# daughter_v1.net
KiCad netlist of a schematic drawn in EAGLE
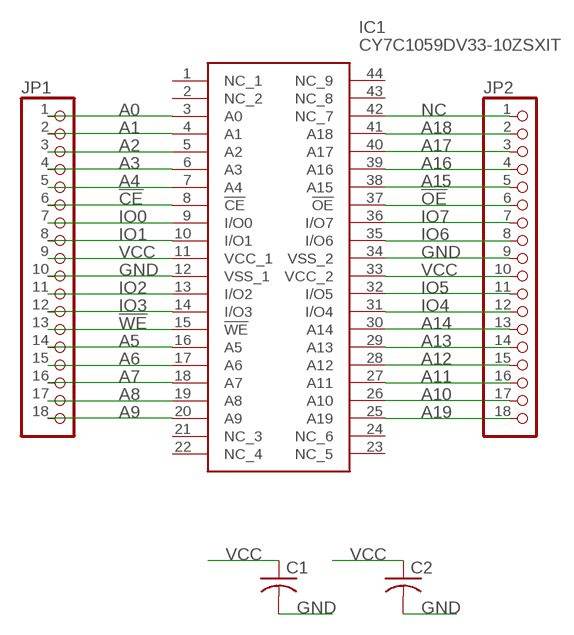
[diagram p0: schematic, sheet 1]

(export (version "E")
  (design (tool "Eeschema 10.0.6"))
  (components
    (comp (ref "C1")
      (value "C-USC0805")
      (footprint "eagle-import:C0805")
      (libsource (lib "eagle-import") (part "C-USC0805"))
    )
    (comp (ref "C2")
      (value "C-USC0805")
      (footprint "eagle-import:C0805")
      (libsource (lib "eagle-import") (part "C-USC0805"))
    )
    (comp (ref "IC1")
      (value "CY7C1059DV33-10ZSXIT")
      (footprint "eagle-import:SOP80P1184X119-44N")
      (fields (field (name "MOUSER_PART_NUMBER") "727-C1059DV3310ZSXIT"))
      (libsource (lib "eagle-import") (part "CY7C1059DV33-10ZSXIT"))
    )
    (comp (ref "JP1")
      (value "PINHD-1X18")
      (footprint "eagle-import:1X18")
      (libsource (lib "eagle-import") (part "PINHD-1X18"))
    )
    (comp (ref "JP2")
      (value "PINHD-1X18")
      (footprint "eagle-import:1X18")
      (libsource (lib "eagle-import") (part "PINHD-1X18"))
    )
  )
  (nets
    (net (code "1") (name "/A0") (class "Default")
      (node (ref "IC1") (pin "3") (pinfunction "A0_3") (pintype "bidirectional"))
      (node (ref "JP1") (pin "1") (pinfunction "1_1") (pintype "passive"))
    )
    (net (code "2") (name "/A1") (class "Default")
      (node (ref "IC1") (pin "4") (pinfunction "A1_4") (pintype "bidirectional"))
      (node (ref "JP1") (pin "2") (pinfunction "2_2") (pintype "passive"))
    )
    (net (code "3") (name "/A2") (class "Default")
      (node (ref "IC1") (pin "5") (pinfunction "A2_5") (pintype "bidirectional"))
      (node (ref "JP1") (pin "3") (pinfunction "3_3") (pintype "passive"))
    )
    (net (code "4") (name "/A3") (class "Default")
      (node (ref "IC1") (pin "6") (pinfunction "A3_6") (pintype "bidirectional"))
      (node (ref "JP1") (pin "4") (pinfunction "4_4") (pintype "passive"))
    )
    (net (code "5") (name "/A4") (class "Default")
      (node (ref "IC1") (pin "7") (pinfunction "A4_7") (pintype "bidirectional"))
      (node (ref "JP1") (pin "5") (pinfunction "5_5") (pintype "passive"))
    )
    (net (code "6") (name "/A5") (class "Default")
      (node (ref "IC1") (pin "16") (pinfunction "A5_16") (pintype "bidirectional"))
      (node (ref "JP1") (pin "14") (pinfunction "14_14") (pintype "passive"))
    )
    (net (code "7") (name "/A6") (class "Default")
      (node (ref "IC1") (pin "17") (pinfunction "A6_17") (pintype "bidirectional"))
      (node (ref "JP1") (pin "15") (pinfunction "15_15") (pintype "passive"))
    )
    (net (code "8") (name "/A7") (class "Default")
      (node (ref "IC1") (pin "18") (pinfunction "A7_18") (pintype "bidirectional"))
      (node (ref "JP1") (pin "16") (pinfunction "16_16") (pintype "passive"))
    )
    (net (code "9") (name "/A8") (class "Default")
      (node (ref "IC1") (pin "19") (pinfunction "A8_19") (pintype "bidirectional"))
      (node (ref "JP1") (pin "17") (pinfunction "17_17") (pintype "passive"))
    )
    (net (code "10") (name "/A9") (class "Default")
      (node (ref "IC1") (pin "20") (pinfunction "A9_20") (pintype "bidirectional"))
      (node (ref "JP1") (pin "18") (pinfunction "18_18") (pintype "passive"))
    )
    (net (code "11") (name "/A10") (class "Default")
      (node (ref "IC1") (pin "26") (pinfunction "A10_26") (pintype "bidirectional"))
      (node (ref "JP2") (pin "17") (pinfunction "17_17") (pintype "passive"))
    )
    (net (code "12") (name "/A11") (class "Default")
      (node (ref "IC1") (pin "27") (pinfunction "A11_27") (pintype "bidirectional"))
      (node (ref "JP2") (pin "16") (pinfunction "16_16") (pintype "passive"))
    )
    (net (code "13") (name "/A12") (class "Default")
      (node (ref "IC1") (pin "28") (pinfunction "A12_28") (pintype "bidirectional"))
      (node (ref "JP2") (pin "15") (pinfunction "15_15") (pintype "passive"))
    )
    (net (code "14") (name "/A13") (class "Default")
      (node (ref "IC1") (pin "29") (pinfunction "A13_29") (pintype "bidirectional"))
      (node (ref "JP2") (pin "14") (pinfunction "14_14") (pintype "passive"))
    )
    (net (code "15") (name "/A14") (class "Default")
      (node (ref "IC1") (pin "30") (pinfunction "A14_30") (pintype "bidirectional"))
      (node (ref "JP2") (pin "13") (pinfunction "13_13") (pintype "passive"))
    )
    (net (code "16") (name "/A15") (class "Default")
      (node (ref "IC1") (pin "38") (pinfunction "A15_38") (pintype "bidirectional"))
      (node (ref "JP2") (pin "5") (pinfunction "5_5") (pintype "passive"))
    )
    (net (code "17") (name "/A16") (class "Default")
      (node (ref "IC1") (pin "39") (pinfunction "A16_39") (pintype "bidirectional"))
      (node (ref "JP2") (pin "4") (pinfunction "4_4") (pintype "passive"))
    )
    (net (code "18") (name "/A17") (class "Default")
      (node (ref "IC1") (pin "40") (pinfunction "A17_40") (pintype "bidirectional"))
      (node (ref "JP2") (pin "3") (pinfunction "3_3") (pintype "passive"))
    )
    (net (code "19") (name "/A18") (class "Default")
      (node (ref "IC1") (pin "41") (pinfunction "A18_41") (pintype "bidirectional"))
      (node (ref "JP2") (pin "2") (pinfunction "2_2") (pintype "passive"))
    )
    (net (code "20") (name "/A19") (class "Default")
      (node (ref "IC1") (pin "25") (pinfunction "A19_25") (pintype "bidirectional"))
      (node (ref "JP2") (pin "18") (pinfunction "18_18") (pintype "passive"))
    )
    (net (code "21") (name "/GND") (class "Default")
      (node (ref "C1") (pin "2") (pinfunction "2_2") (pintype "passive"))
      (node (ref "C2") (pin "2") (pinfunction "2_2") (pintype "passive"))
      (node (ref "IC1") (pin "12") (pinfunction "VSS_1_12") (pintype "bidirectional"))
      (node (ref "IC1") (pin "34") (pinfunction "VSS_2_34") (pintype "bidirectional"))
      (node (ref "JP1") (pin "10") (pinfunction "10_10") (pintype "passive"))
      (node (ref "JP2") (pin "9") (pinfunction "9_9") (pintype "passive"))
    )
    (net (code "22") (name "/IO0") (class "Default")
      (node (ref "IC1") (pin "9") (pinfunction "I/O0_9") (pintype "bidirectional"))
      (node (ref "JP1") (pin "7") (pinfunction "7_7") (pintype "passive"))
    )
    (net (code "23") (name "/IO1") (class "Default")
      (node (ref "IC1") (pin "10") (pinfunction "I/O1_10") (pintype "bidirectional"))
      (node (ref "JP1") (pin "8") (pinfunction "8_8") (pintype "passive"))
    )
    (net (code "24") (name "/IO2") (class "Default")
      (node (ref "IC1") (pin "13") (pinfunction "I/O2_13") (pintype "bidirectional"))
      (node (ref "JP1") (pin "11") (pinfunction "11_11") (pintype "passive"))
    )
    (net (code "25") (name "/IO3") (class "Default")
      (node (ref "IC1") (pin "14") (pinfunction "I/O3_14") (pintype "bidirectional"))
      (node (ref "JP1") (pin "12") (pinfunction "12_12") (pintype "passive"))
    )
    (net (code "26") (name "/IO4") (class "Default")
      (node (ref "IC1") (pin "31") (pinfunction "I/O4_31") (pintype "bidirectional"))
      (node (ref "JP2") (pin "12") (pinfunction "12_12") (pintype "passive"))
    )
    (net (code "27") (name "/IO5") (class "Default")
      (node (ref "IC1") (pin "32") (pinfunction "I/O5_32") (pintype "bidirectional"))
      (node (ref "JP2") (pin "11") (pinfunction "11_11") (pintype "passive"))
    )
    (net (code "28") (name "/IO6") (class "Default")
      (node (ref "IC1") (pin "35") (pinfunction "I/O6_35") (pintype "bidirectional"))
      (node (ref "JP2") (pin "8") (pinfunction "8_8") (pintype "passive"))
    )
    (net (code "29") (name "/IO7") (class "Default")
      (node (ref "IC1") (pin "36") (pinfunction "I/O7_36") (pintype "bidirectional"))
      (node (ref "JP2") (pin "7") (pinfunction "7_7") (pintype "passive"))
    )
    (net (code "30") (name "/NC") (class "Default")
      (node (ref "IC1") (pin "42") (pinfunction "NC_7_42") (pintype "bidirectional"))
      (node (ref "JP2") (pin "1") (pinfunction "1_1") (pintype "passive"))
    )
    (net (code "31") (name "/VCC") (class "Default")
      (node (ref "C1") (pin "1") (pinfunction "1_1") (pintype "passive"))
      (node (ref "C2") (pin "1") (pinfunction "1_1") (pintype "passive"))
      (node (ref "IC1") (pin "11") (pinfunction "VCC_1_11") (pintype "bidirectional"))
      (node (ref "IC1") (pin "33") (pinfunction "VCC_2_33") (pintype "bidirectional"))
      (node (ref "JP1") (pin "9") (pinfunction "9_9") (pintype "passive"))
      (node (ref "JP2") (pin "10") (pinfunction "10_10") (pintype "passive"))
    )
    (net (code "32") (name "/~{CE}") (class "Default")
      (node (ref "IC1") (pin "8") (pinfunction "~{CE}_8") (pintype "bidirectional"))
      (node (ref "JP1") (pin "6") (pinfunction "6_6") (pintype "passive"))
    )
    (net (code "33") (name "/~{OE}") (class "Default")
      (node (ref "IC1") (pin "37") (pinfunction "~{OE}_37") (pintype "bidirectional"))
      (node (ref "JP2") (pin "6") (pinfunction "6_6") (pintype "passive"))
    )
    (net (code "34") (name "/~{WE}") (class "Default")
      (node (ref "IC1") (pin "15") (pinfunction "~{WE}_15") (pintype "bidirectional"))
      (node (ref "JP1") (pin "13") (pinfunction "13_13") (pintype "passive"))
    )
    (net (code "35") (name "unconnected-(IC1-NC_1-Pad1)") (class "Default")
      (node (ref "IC1") (pin "1") (pinfunction "NC_1_1") (pintype "bidirectional"))
    )
    (net (code "36") (name "unconnected-(IC1-NC_2-Pad2)") (class "Default")
      (node (ref "IC1") (pin "2") (pinfunction "NC_2_2") (pintype "bidirectional"))
    )
    (net (code "37") (name "unconnected-(IC1-NC_3-Pad21)") (class "Default")
      (node (ref "IC1") (pin "21") (pinfunction "NC_3_21") (pintype "bidirectional"))
    )
    (net (code "38") (name "unconnected-(IC1-NC_4-Pad22)") (class "Default")
      (node (ref "IC1") (pin "22") (pinfunction "NC_4_22") (pintype "bidirectional"))
    )
    (net (code "39") (name "unconnected-(IC1-NC_5-Pad23)") (class "Default")
      (node (ref "IC1") (pin "23") (pinfunction "NC_5_23") (pintype "bidirectional"))
    )
    (net (code "40") (name "unconnected-(IC1-NC_6-Pad24)") (class "Default")
      (node (ref "IC1") (pin "24") (pinfunction "NC_6_24") (pintype "bidirectional"))
    )
    (net (code "41") (name "unconnected-(IC1-NC_8-Pad43)") (class "Default")
      (node (ref "IC1") (pin "43") (pinfunction "NC_8_43") (pintype "bidirectional"))
    )
    (net (code "42") (name "unconnected-(IC1-NC_9-Pad44)") (class "Default")
      (node (ref "IC1") (pin "44") (pinfunction "NC_9_44") (pintype "bidirectional"))
    )
  )
)
